# 9DoF_Sensor_Stick.net
KiCad netlist of a schematic drawn in EAGLE
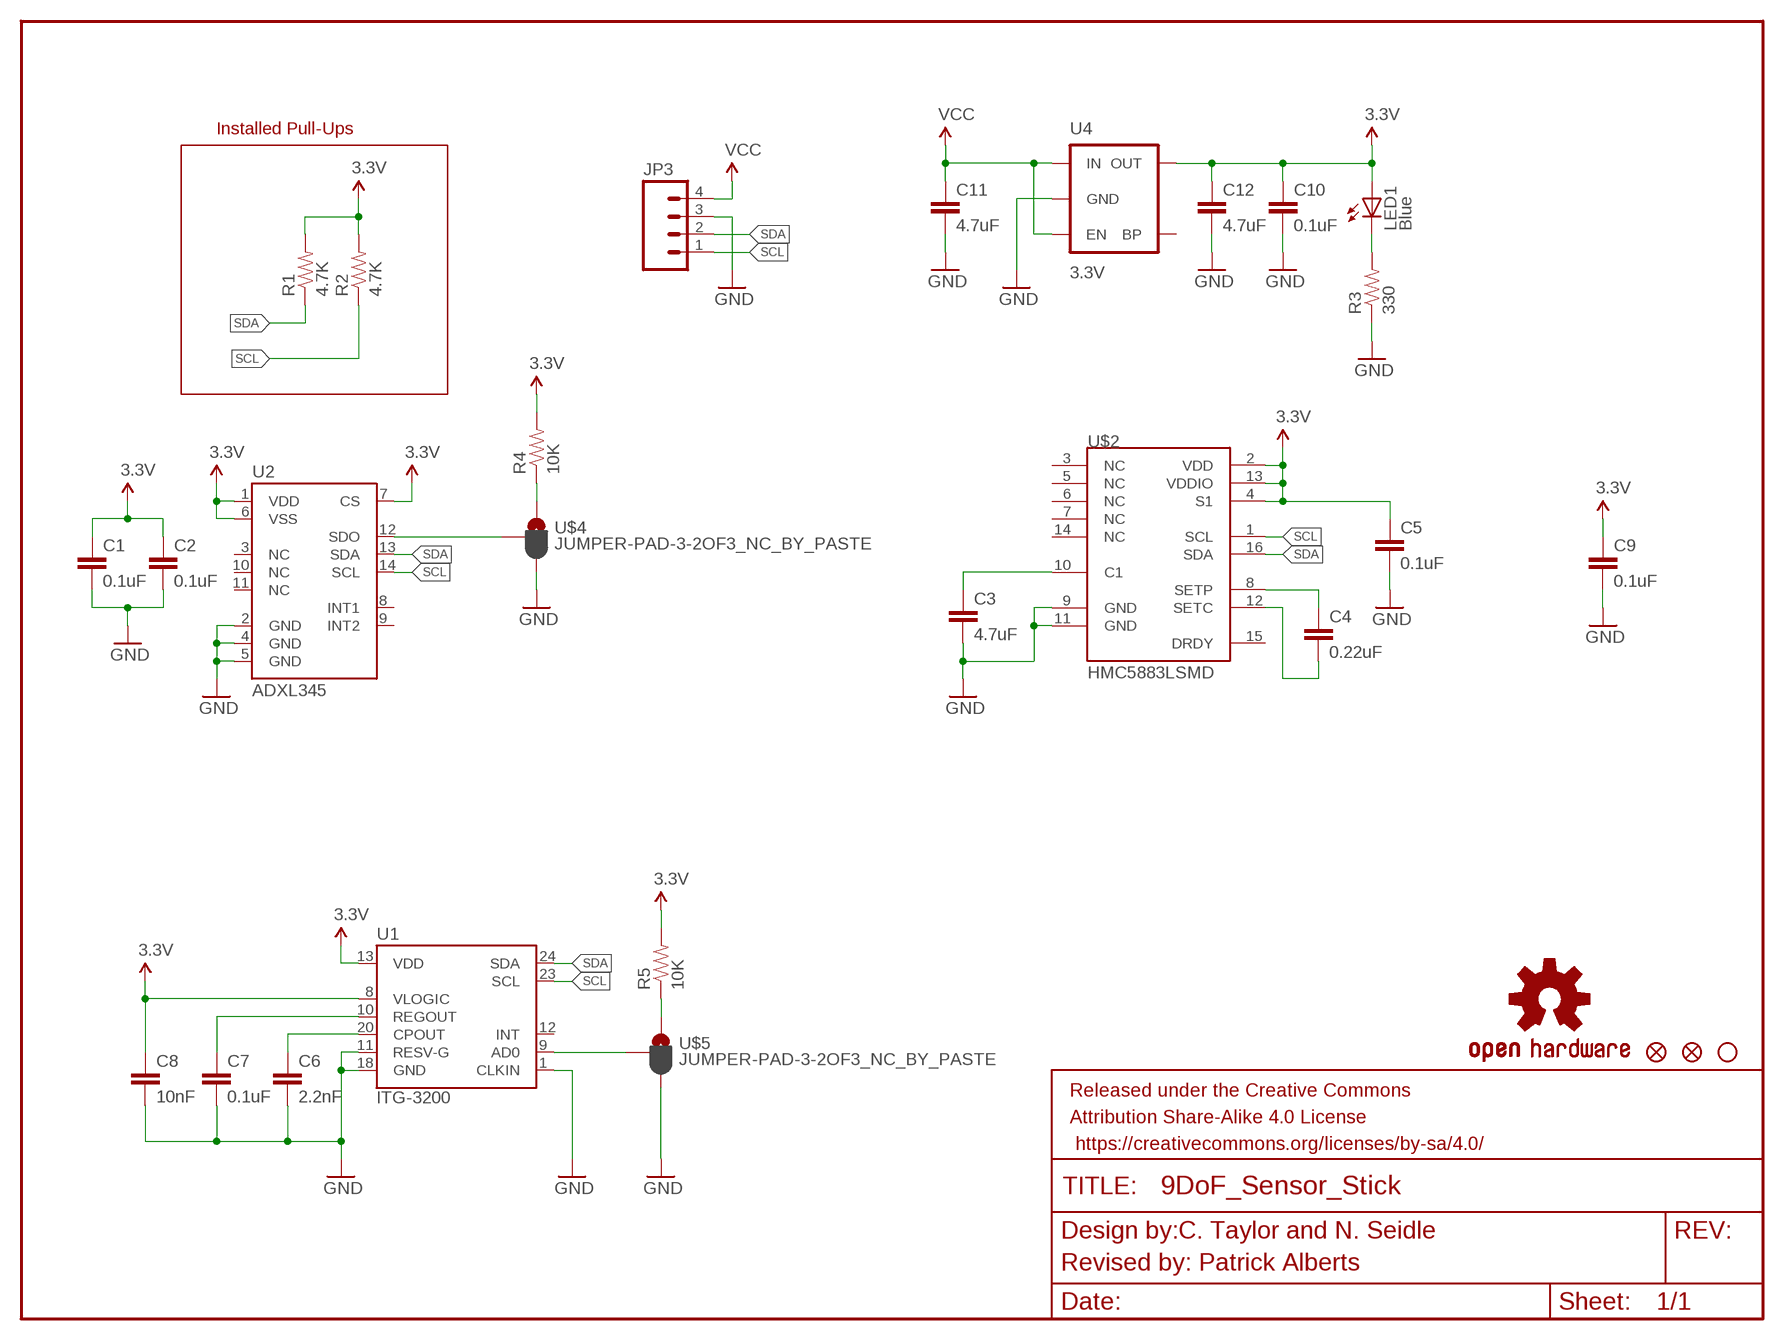
[diagram p0: schematic, sheet 1]

(export (version "E")
  (design (tool "Eeschema 10.0.6"))
  (components
    (comp (ref "C1")
      (value "0.1uF")
      (footprint "eagle-import:0603-CAP")
      (libsource (lib "eagle-import") (part "0.1UF-25V(+80/-20%)(0603)"))
    )
    (comp (ref "C2")
      (value "0.1uF")
      (footprint "eagle-import:0603-CAP")
      (libsource (lib "eagle-import") (part "0.1UF-25V(+80/-20%)(0603)"))
    )
    (comp (ref "C3")
      (value "4.7uF")
      (footprint "eagle-import:0603-CAP")
      (libsource (lib "eagle-import") (part "4.7UF-6.3V-10%(0603)0603"))
    )
    (comp (ref "C4")
      (value "0.22uF")
      (footprint "eagle-import:0603-CAP")
      (libsource (lib "eagle-import") (part "0.22UF-25V-10%(0603)"))
    )
    (comp (ref "C5")
      (value "0.1uF")
      (footprint "eagle-import:0603-CAP")
      (libsource (lib "eagle-import") (part "0.1UF-25V(+80/-20%)(0603)"))
    )
    (comp (ref "C6")
      (value "2.2nF")
      (footprint "eagle-import:0603-CAP")
      (libsource (lib "eagle-import") (part "2.2NF/2200PF-50V-10%(0603)"))
    )
    (comp (ref "C7")
      (value "0.1uF")
      (footprint "eagle-import:0603-CAP")
      (libsource (lib "eagle-import") (part "0.1UF-25V(+80/-20%)(0603)"))
    )
    (comp (ref "C8")
      (value "10nF")
      (footprint "eagle-import:0603-CAP")
      (libsource (lib "eagle-import") (part "10NF/10000PF-50V-10%(0603)"))
    )
    (comp (ref "C9")
      (value "0.1uF")
      (footprint "eagle-import:0603-CAP")
      (libsource (lib "eagle-import") (part "0.1UF-25V(+80/-20%)(0603)"))
    )
    (comp (ref "C10")
      (value "0.1uF")
      (footprint "eagle-import:0603-CAP")
      (libsource (lib "eagle-import") (part "0.1UF-25V(+80/-20%)(0603)"))
    )
    (comp (ref "C11")
      (value "4.7uF")
      (footprint "eagle-import:0603-CAP")
      (libsource (lib "eagle-import") (part "4.7UF-6.3V-10%(0603)0603"))
    )
    (comp (ref "C12")
      (value "4.7uF")
      (footprint "eagle-import:0603-CAP")
      (libsource (lib "eagle-import") (part "4.7UF-6.3V-10%(0603)0603"))
    )
    (comp (ref "FRAME1")
      (value "FRAME-LETTER")
      (footprint "eagle-import:CREATIVE_COMMONS")
      (libsource (lib "eagle-import") (part "FRAME-LETTER"))
    )
    (comp (ref "JP1")
      (value "FIDUCIAL1X2")
      (footprint "eagle-import:FIDUCIAL-1X2")
      (libsource (lib "eagle-import") (part "FIDUCIAL1X2"))
    )
    (comp (ref "JP2")
      (value "FIDUCIAL1X2")
      (footprint "eagle-import:FIDUCIAL-1X2")
      (libsource (lib "eagle-import") (part "FIDUCIAL1X2"))
    )
    (comp (ref "JP3")
      (value "M04PTH")
      (footprint "eagle-import:1X04")
      (libsource (lib "eagle-import") (part "M04PTH"))
    )
    (comp (ref "JP5")
      (value "STAND-OFF")
      (footprint "eagle-import:STAND-OFF")
      (libsource (lib "eagle-import") (part "STAND-OFF"))
    )
    (comp (ref "LED1")
      (value "Blue")
      (footprint "eagle-import:LED-0603")
      (libsource (lib "eagle-import") (part "LED0603"))
    )
    (comp (ref "R1")
      (value "4.7K")
      (footprint "eagle-import:0603")
      (libsource (lib "eagle-import") (part "4.7KOHM1/10W1%(0603)"))
    )
    (comp (ref "R2")
      (value "4.7K")
      (footprint "eagle-import:0603")
      (libsource (lib "eagle-import") (part "4.7KOHM1/10W1%(0603)"))
    )
    (comp (ref "R3")
      (value "330")
      (footprint "eagle-import:0603-RES")
      (libsource (lib "eagle-import") (part "330OHM1/10W1%(0603)"))
    )
    (comp (ref "R4")
      (value "10K")
      (footprint "eagle-import:0603-RES")
      (libsource (lib "eagle-import") (part "10KOHM1/10W1%(0603)0603"))
    )
    (comp (ref "R5")
      (value "10K")
      (footprint "eagle-import:0603-RES")
      (libsource (lib "eagle-import") (part "10KOHM1/10W1%(0603)0603"))
    )
    (comp (ref "U$2")
      (value "HMC5883LSMD")
      (footprint "eagle-import:16LPCC")
      (libsource (lib "eagle-import") (part "HMC5883LSMD"))
    )
    (comp (ref "U$3")
      (value "OSHW-LOGOS")
      (footprint "eagle-import:OSHW-LOGO-S")
      (libsource (lib "eagle-import") (part "OSHW-LOGOS"))
    )
    (comp (ref "U$4")
      (value "JUMPER-PAD-3-2OF3_NC_BY_PASTE")
      (footprint "eagle-import:PAD-JUMPER-3-2OF3_NC_BY_PASTE_YES_SILK_FULL_BOX")
      (libsource (lib "eagle-import") (part "JUMPER-PAD-3-2OF3_NC_BY_PASTE"))
    )
    (comp (ref "U$5")
      (value "JUMPER-PAD-3-2OF3_NC_BY_PASTE")
      (footprint "eagle-import:PAD-JUMPER-3-2OF3_NC_BY_PASTE_YES_SILK_FULL_BOX")
      (libsource (lib "eagle-import") (part "JUMPER-PAD-3-2OF3_NC_BY_PASTE"))
    )
    (comp (ref "U1")
      (value "ITG-3200")
      (footprint "eagle-import:QFN-24")
      (libsource (lib "eagle-import") (part "ITG-3200"))
    )
    (comp (ref "U2")
      (value "ADXL345")
      (footprint "eagle-import:LGA14")
      (libsource (lib "eagle-import") (part "ADXL345"))
    )
    (comp (ref "U4")
      (value "3.3V")
      (footprint "eagle-import:SOT23-5")
      (libsource (lib "eagle-import") (part "V_REG_LDOSMD"))
    )
  )
  (nets
    (net (code "1") (name "3.3V") (class "Default")
      (node (ref "C1") (pin "1") (pinfunction "1_1") (pintype "passive"))
      (node (ref "C10") (pin "1") (pinfunction "1_1") (pintype "passive"))
      (node (ref "C12") (pin "1") (pinfunction "1_1") (pintype "passive"))
      (node (ref "C2") (pin "1") (pinfunction "1_1") (pintype "passive"))
      (node (ref "C5") (pin "1") (pinfunction "1_1") (pintype "passive"))
      (node (ref "C8") (pin "1") (pinfunction "1_1") (pintype "passive"))
      (node (ref "C9") (pin "1") (pinfunction "1_1") (pintype "passive"))
      (node (ref "LED1") (pin "A") (pinfunction "A_A") (pintype "passive"))
      (node (ref "R1") (pin "2") (pinfunction "2_2") (pintype "passive"))
      (node (ref "R2") (pin "2") (pinfunction "2_2") (pintype "passive"))
      (node (ref "R4") (pin "2") (pinfunction "2_2") (pintype "passive"))
      (node (ref "R5") (pin "2") (pinfunction "2_2") (pintype "passive"))
      (node (ref "U$2") (pin "13") (pinfunction "VDDIO_13") (pintype "bidirectional"))
      (node (ref "U$2") (pin "2") (pinfunction "VDD_2") (pintype "bidirectional"))
      (node (ref "U$2") (pin "4") (pinfunction "S1_4") (pintype "bidirectional"))
      (node (ref "U1") (pin "13") (pinfunction "VDD_13") (pintype "bidirectional"))
      (node (ref "U1") (pin "8") (pinfunction "VLOGIC_8") (pintype "bidirectional"))
      (node (ref "U2") (pin "1") (pinfunction "VDD_1") (pintype "bidirectional"))
      (node (ref "U2") (pin "6") (pinfunction "VSS_6") (pintype "bidirectional"))
      (node (ref "U2") (pin "7") (pinfunction "CS_7") (pintype "bidirectional"))
      (node (ref "U4") (pin "5") (pinfunction "OUT_5") (pintype "passive"))
    )
    (net (code "2") (name "GND") (class "Default")
      (node (ref "C1") (pin "2") (pinfunction "2_2") (pintype "passive"))
      (node (ref "C10") (pin "2") (pinfunction "2_2") (pintype "passive"))
      (node (ref "C11") (pin "2") (pinfunction "2_2") (pintype "passive"))
      (node (ref "C12") (pin "2") (pinfunction "2_2") (pintype "passive"))
      (node (ref "C2") (pin "2") (pinfunction "2_2") (pintype "passive"))
      (node (ref "C3") (pin "2") (pinfunction "2_2") (pintype "passive"))
      (node (ref "C5") (pin "2") (pinfunction "2_2") (pintype "passive"))
      (node (ref "C6") (pin "2") (pinfunction "2_2") (pintype "passive"))
      (node (ref "C7") (pin "2") (pinfunction "2_2") (pintype "passive"))
      (node (ref "C8") (pin "2") (pinfunction "2_2") (pintype "passive"))
      (node (ref "C9") (pin "2") (pinfunction "2_2") (pintype "passive"))
      (node (ref "JP3") (pin "3") (pinfunction "3_3") (pintype "passive"))
      (node (ref "R3") (pin "1") (pinfunction "1_1") (pintype "passive"))
      (node (ref "U$2") (pin "11") (pinfunction "GND_11") (pintype "bidirectional"))
      (node (ref "U$2") (pin "9") (pinfunction "GND_9") (pintype "bidirectional"))
      (node (ref "U$4") (pin "3") (pinfunction "3_3") (pintype "passive"))
      (node (ref "U$5") (pin "3") (pinfunction "3_3") (pintype "passive"))
      (node (ref "U1") (pin "1") (pinfunction "CLKIN_1") (pintype "bidirectional"))
      (node (ref "U1") (pin "11") (pinfunction "RESV-G_11") (pintype "bidirectional"))
      (node (ref "U1") (pin "18") (pinfunction "GND_18") (pintype "bidirectional"))
      (node (ref "U2") (pin "2") (pinfunction "GND_2") (pintype "bidirectional"))
      (node (ref "U2") (pin "4") (pinfunction "GND_4") (pintype "bidirectional"))
      (node (ref "U2") (pin "5") (pinfunction "GND_5") (pintype "bidirectional"))
      (node (ref "U4") (pin "2") (pinfunction "GND_2") (pintype "input"))
    )
    (net (code "3") (name "Net-(LED1-PadC)") (class "Default")
      (node (ref "LED1") (pin "C") (pinfunction "C_C") (pintype "passive"))
      (node (ref "R3") (pin "2") (pinfunction "2_2") (pintype "passive"))
    )
    (net (code "4") (name "Net-(R4-Pad1)") (class "Default")
      (node (ref "R4") (pin "1") (pinfunction "1_1") (pintype "passive"))
      (node (ref "U$4") (pin "1") (pinfunction "1_1") (pintype "passive"))
    )
    (net (code "5") (name "Net-(R5-Pad1)") (class "Default")
      (node (ref "R5") (pin "1") (pinfunction "1_1") (pintype "passive"))
      (node (ref "U$5") (pin "1") (pinfunction "1_1") (pintype "passive"))
    )
    (net (code "6") (name "Net-(U$2-C1)") (class "Default")
      (node (ref "C3") (pin "1") (pinfunction "1_1") (pintype "passive"))
      (node (ref "U$2") (pin "10") (pinfunction "C1_10") (pintype "bidirectional"))
    )
    (net (code "7") (name "Net-(U$2-SETC)") (class "Default")
      (node (ref "C4") (pin "2") (pinfunction "2_2") (pintype "passive"))
      (node (ref "U$2") (pin "12") (pinfunction "SETC_12") (pintype "bidirectional"))
    )
    (net (code "8") (name "Net-(U$2-SETP)") (class "Default")
      (node (ref "C4") (pin "1") (pinfunction "1_1") (pintype "passive"))
      (node (ref "U$2") (pin "8") (pinfunction "SETP_8") (pintype "bidirectional"))
    )
    (net (code "9") (name "Net-(U1-AD0)") (class "Default")
      (node (ref "U$5") (pin "2") (pinfunction "2_2") (pintype "passive"))
      (node (ref "U1") (pin "9") (pinfunction "AD0_9") (pintype "bidirectional"))
    )
    (net (code "10") (name "Net-(U1-CPOUT)") (class "Default")
      (node (ref "C6") (pin "1") (pinfunction "1_1") (pintype "passive"))
      (node (ref "U1") (pin "20") (pinfunction "CPOUT_20") (pintype "bidirectional"))
    )
    (net (code "11") (name "Net-(U1-REGOUT)") (class "Default")
      (node (ref "C7") (pin "1") (pinfunction "1_1") (pintype "passive"))
      (node (ref "U1") (pin "10") (pinfunction "REGOUT_10") (pintype "bidirectional"))
    )
    (net (code "12") (name "Net-(U2-SDO)") (class "Default")
      (node (ref "U$4") (pin "2") (pinfunction "2_2") (pintype "passive"))
      (node (ref "U2") (pin "12") (pinfunction "SDO_12") (pintype "bidirectional"))
    )
    (net (code "13") (name "SCL") (class "Default")
      (node (ref "JP3") (pin "1") (pinfunction "1_1") (pintype "passive"))
      (node (ref "R2") (pin "1") (pinfunction "1_1") (pintype "passive"))
      (node (ref "U$2") (pin "1") (pinfunction "SCL_1") (pintype "bidirectional"))
      (node (ref "U1") (pin "23") (pinfunction "SCL_23") (pintype "bidirectional"))
      (node (ref "U2") (pin "14") (pinfunction "SCL_14") (pintype "bidirectional"))
    )
    (net (code "14") (name "SDA") (class "Default")
      (node (ref "JP3") (pin "2") (pinfunction "2_2") (pintype "passive"))
      (node (ref "R1") (pin "1") (pinfunction "1_1") (pintype "passive"))
      (node (ref "U$2") (pin "16") (pinfunction "SDA_16") (pintype "bidirectional"))
      (node (ref "U1") (pin "24") (pinfunction "SDA_24") (pintype "bidirectional"))
      (node (ref "U2") (pin "13") (pinfunction "SDA_13") (pintype "bidirectional"))
    )
    (net (code "15") (name "VCC") (class "Default")
      (node (ref "C11") (pin "1") (pinfunction "1_1") (pintype "passive"))
      (node (ref "JP3") (pin "4") (pinfunction "4_4") (pintype "passive"))
      (node (ref "U4") (pin "1") (pinfunction "IN_1") (pintype "input"))
      (node (ref "U4") (pin "3") (pinfunction "EN_3") (pintype "input"))
    )
    (net (code "16") (name "unconnected-(U$2-DRDY-Pad15)") (class "Default")
      (node (ref "U$2") (pin "15") (pinfunction "DRDY_15") (pintype "bidirectional"))
    )
    (net (code "17") (name "unconnected-(U$2-NC-Pad3)") (class "Default")
      (node (ref "U$2") (pin "3") (pinfunction "NC_3") (pintype "bidirectional"))
    )
    (net (code "18") (name "unconnected-(U$2-NC-Pad5)") (class "Default")
      (node (ref "U$2") (pin "5") (pinfunction "NC_5") (pintype "bidirectional"))
    )
    (net (code "19") (name "unconnected-(U$2-NC-Pad6)") (class "Default")
      (node (ref "U$2") (pin "6") (pinfunction "NC_6") (pintype "bidirectional"))
    )
    (net (code "20") (name "unconnected-(U$2-NC-Pad7)") (class "Default")
      (node (ref "U$2") (pin "7") (pinfunction "NC_7") (pintype "bidirectional"))
    )
    (net (code "21") (name "unconnected-(U$2-NC-Pad14)") (class "Default")
      (node (ref "U$2") (pin "14") (pinfunction "NC_14") (pintype "bidirectional"))
    )
    (net (code "22") (name "unconnected-(U1-INT-Pad12)") (class "Default")
      (node (ref "U1") (pin "12") (pinfunction "INT_12") (pintype "bidirectional"))
    )
    (net (code "23") (name "unconnected-(U2-INT1-Pad8)") (class "Default")
      (node (ref "U2") (pin "8") (pinfunction "INT1_8") (pintype "bidirectional"))
    )
    (net (code "24") (name "unconnected-(U2-INT2-Pad9)") (class "Default")
      (node (ref "U2") (pin "9") (pinfunction "INT2_9") (pintype "bidirectional"))
    )
    (net (code "25") (name "unconnected-(U2-NC-Pad3)") (class "Default")
      (node (ref "U2") (pin "3") (pinfunction "NC_3") (pintype "bidirectional"))
    )
    (net (code "26") (name "unconnected-(U2-NC-Pad10)") (class "Default")
      (node (ref "U2") (pin "10") (pinfunction "NC_10") (pintype "bidirectional"))
    )
    (net (code "27") (name "unconnected-(U2-NC-Pad11)") (class "Default")
      (node (ref "U2") (pin "11") (pinfunction "NC_11") (pintype "bidirectional"))
    )
    (net (code "28") (name "unconnected-(U4-BP-Pad4)") (class "Default")
      (node (ref "U4") (pin "4") (pinfunction "BP_4") (pintype "input"))
    )
  )
)
